# M66_Quectel.net
KiCad netlist of a schematic drawn in Altium Designer
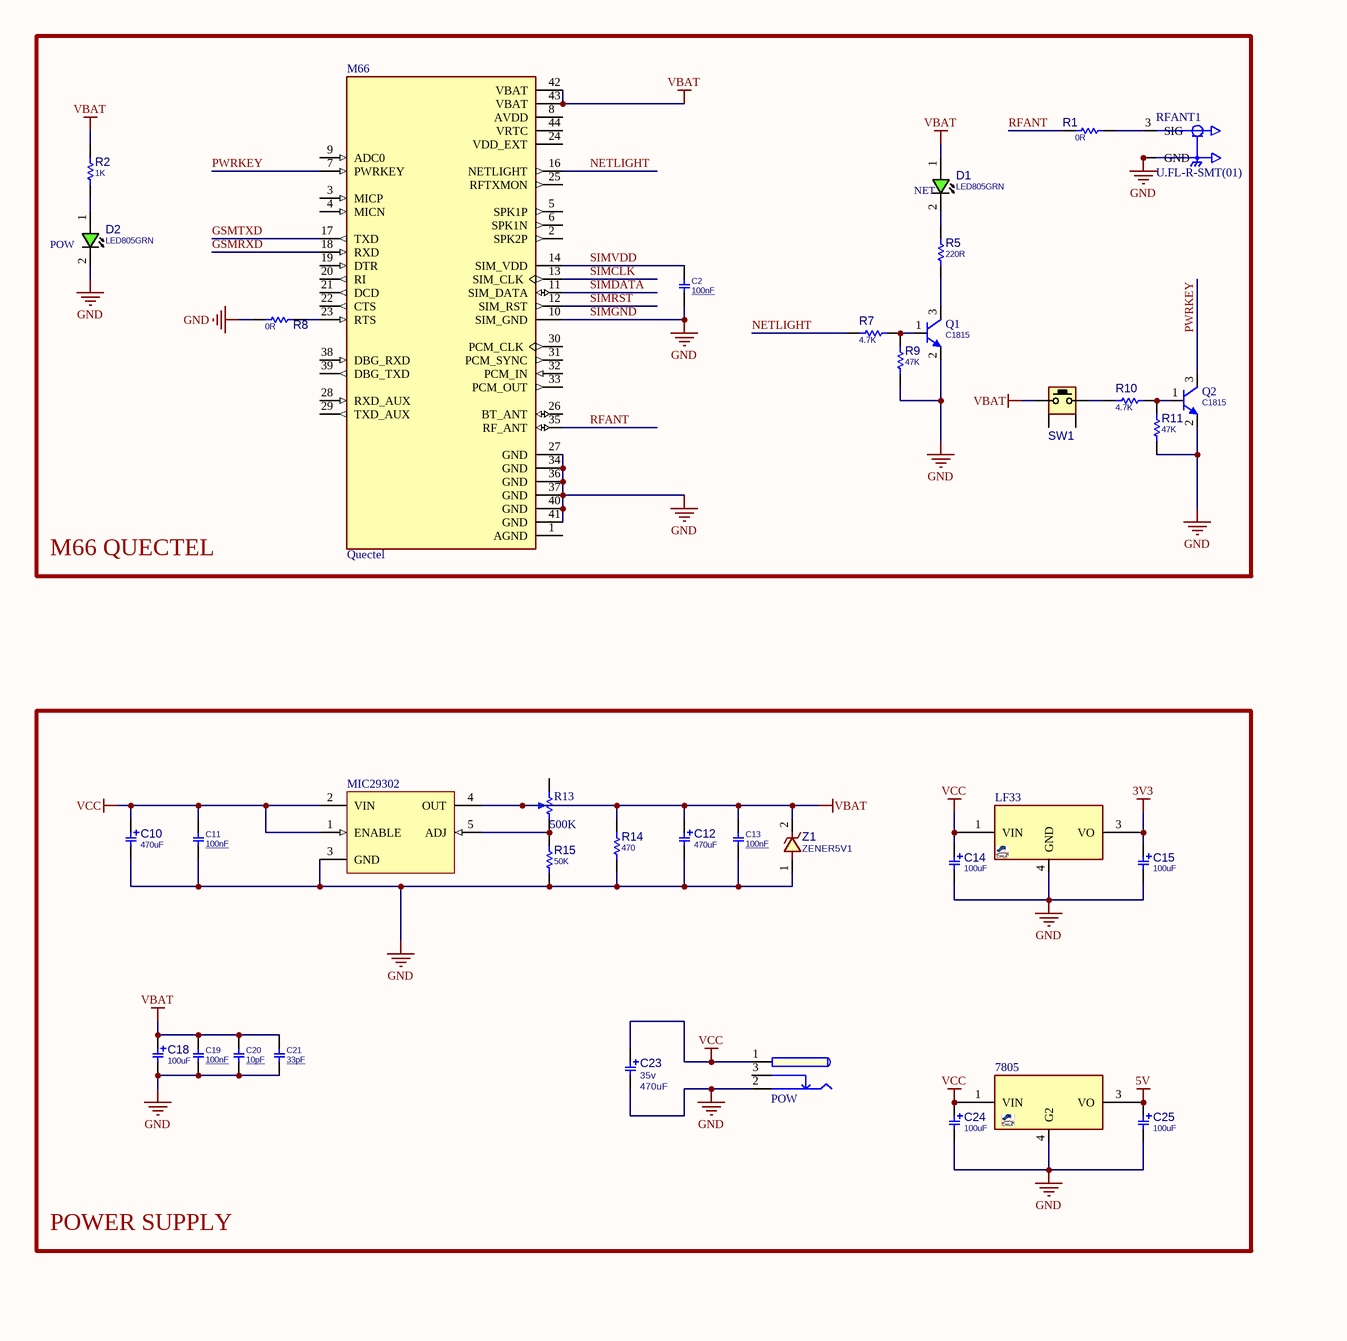
[diagram p0: M66 Quectel.SchDoc, left]
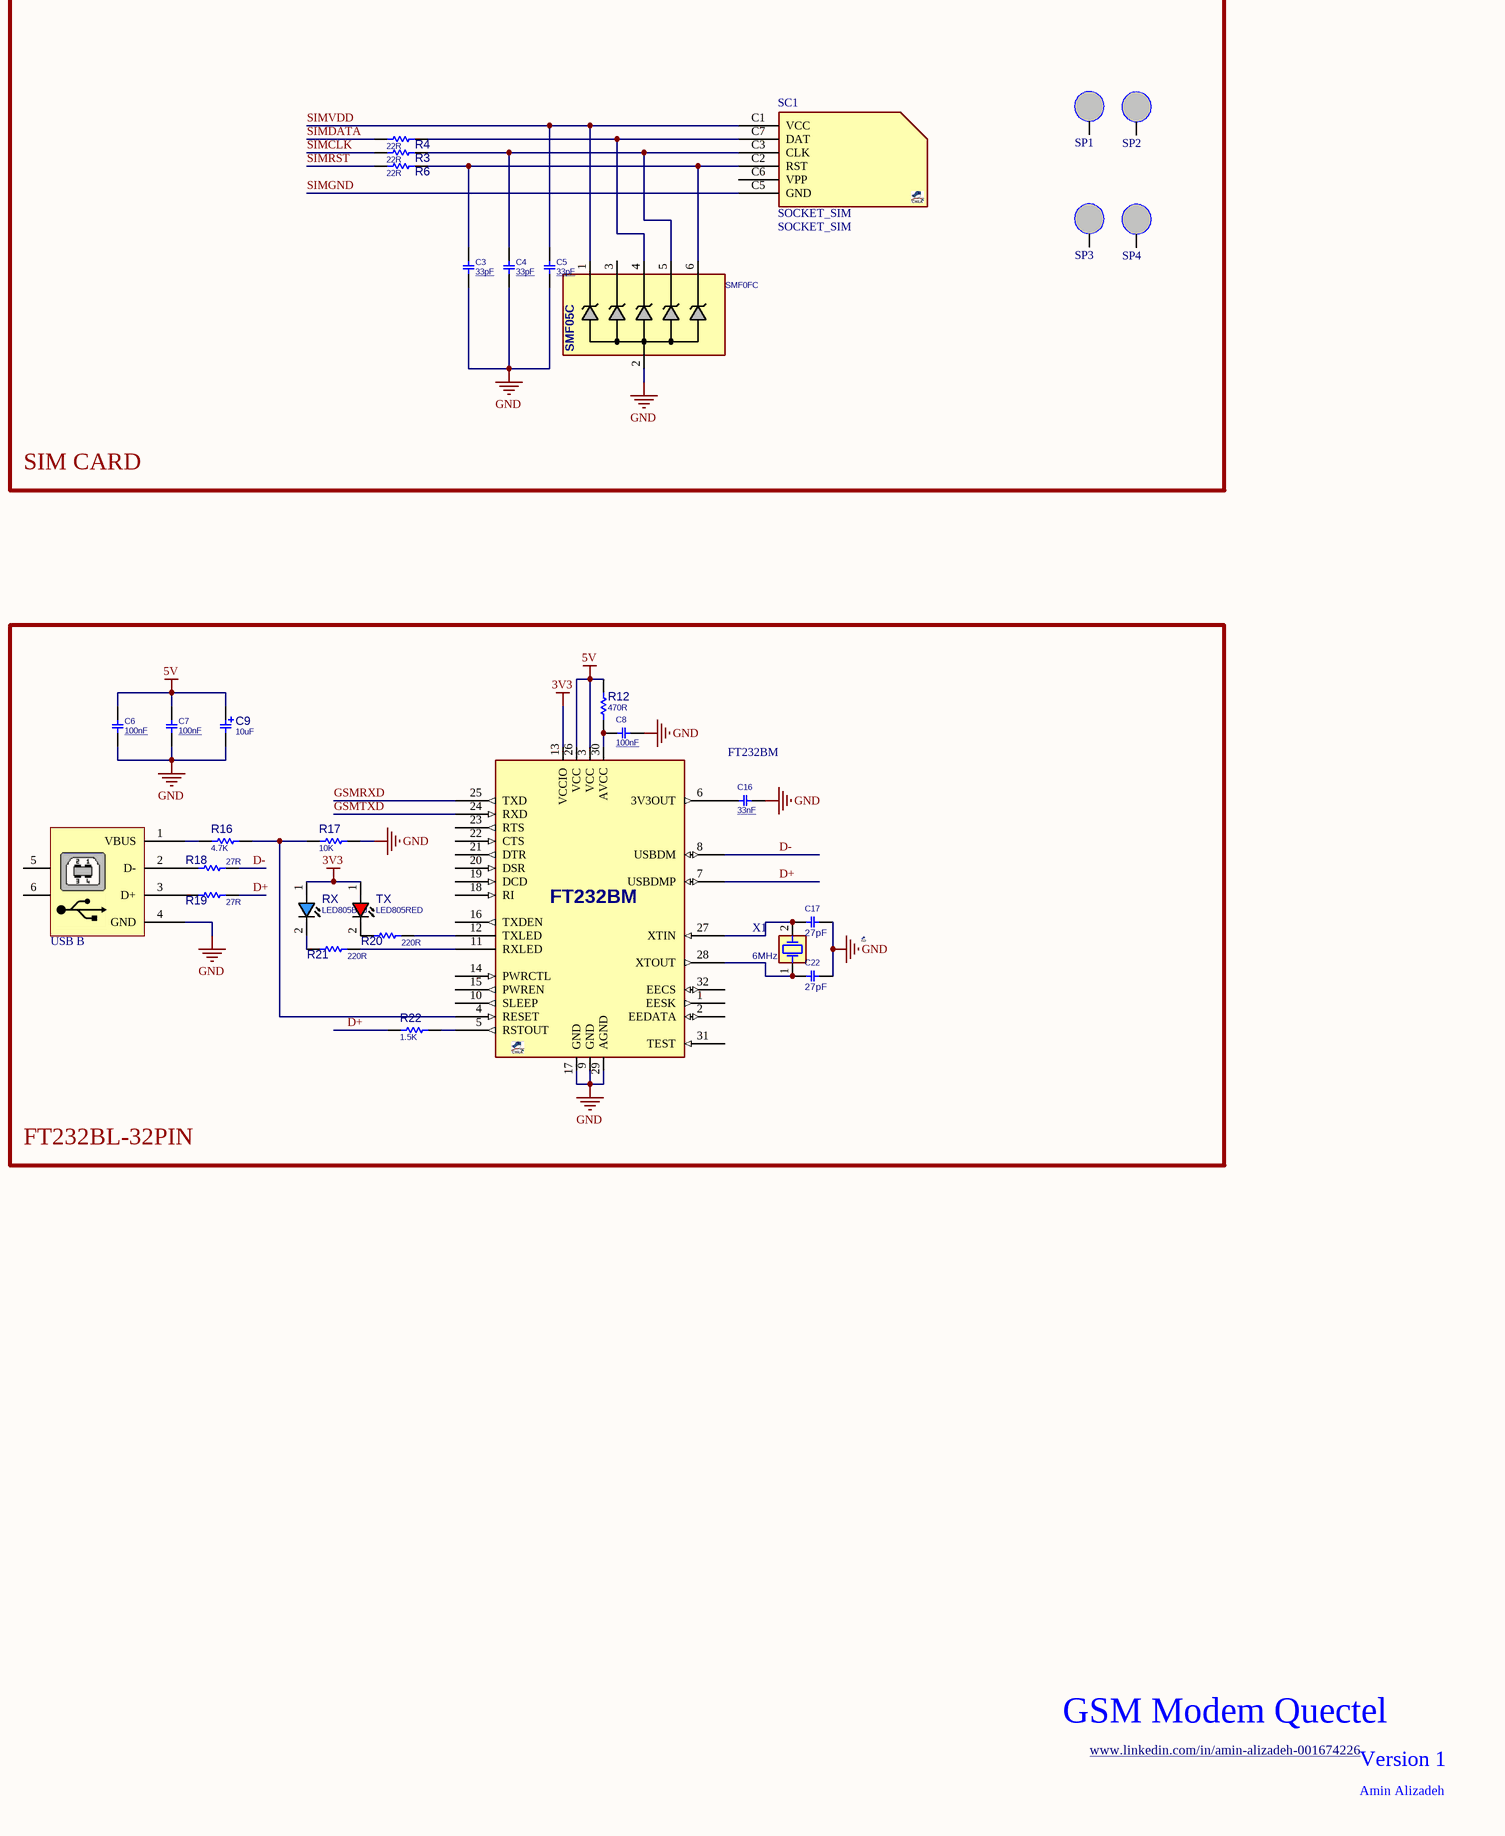
[diagram p1: M66 Quectel.SchDoc, right]

(export (version "E")
  (design (tool "Eeschema 10.0.6"))
  (components
    (comp (ref "7805")
      (value "7805")
      (footprint "D2PAK_2")
      (description "REG, Linear, Fixed, 5v, 1A, TO-263")
      (fields (field (name "MANF_P#") "L7805ABD2T") (field (name "MANF") "TI"))
      (libsource (lib "pwr_reg_linear_78xx79xx") (part "VREG_L7805A_TO263"))
    )
    (comp (ref "C2")
      (value "100nF")
      (footprint "C0805")
      (description "CAP, MLCC, -F, -V, MATERIAL, -%, 0201")
      (fields (field (name "MANF_P#") "MANF_PART#"))
      (libsource (lib "passive_smd") (part "CAP_SMD_MLCC_0805"))
    )
    (comp (ref "C3")
      (value "33pF")
      (footprint "C0805")
      (description "CAP, MLCC, -F, -V, MATERIAL, -%, 0201")
      (fields (field (name "MANF_P#") "MANF_PART#"))
      (libsource (lib "passive_smd") (part "CAP_SMD_MLCC_0805"))
    )
    (comp (ref "C4")
      (value "33pF")
      (footprint "C0805")
      (description "CAP, MLCC, -F, -V, MATERIAL, -%, 0201")
      (fields (field (name "MANF_P#") "MANF_PART#"))
      (libsource (lib "passive_smd") (part "CAP_SMD_MLCC_0805"))
    )
    (comp (ref "C5")
      (value "33pF")
      (footprint "C0805")
      (description "CAP, MLCC, -F, -V, MATERIAL, -%, 0201")
      (fields (field (name "MANF_P#") "MANF_PART#"))
      (libsource (lib "passive_smd") (part "CAP_SMD_MLCC_0805"))
    )
    (comp (ref "C6")
      (value "100nF")
      (footprint "C0805")
      (description "CAP, MLCC, -F, -V, MATERIAL, -%, 0201")
      (fields (field (name "MANF_P#") "MANF_PART#"))
      (libsource (lib "passive_smd") (part "CAP_SMD_MLCC_0805"))
    )
    (comp (ref "C7")
      (value "100nF")
      (footprint "C0805")
      (description "CAP, MLCC, -F, -V, MATERIAL, -%, 0201")
      (fields (field (name "MANF_P#") "MANF_PART#"))
      (libsource (lib "passive_smd") (part "CAP_SMD_MLCC_0805"))
    )
    (comp (ref "C8")
      (value "100nF")
      (footprint "C0805")
      (description "CAP, MLCC, -F, -V, MATERIAL, -%, 0201")
      (fields (field (name "MANF_P#") "MANF_PART#"))
      (libsource (lib "passive_smd") (part "CAP_SMD_MLCC_0805"))
    )
    (comp (ref "C9")
      (value "10uF")
      (footprint "SMD_Cap_10x10")
      (description "CAP, THD, ELEC,")
      (fields (field (name "MANF_P#") "MANF_PART#") (field (name "MANF") "MANF"))
      (libsource (lib "passive_smd") (part "CAP_SMD_EL_8"))
    )
    (comp (ref "C10")
      (value "470uF")
      (footprint "SMD_Cap_10x10")
      (description "CAP, THD, ELEC,")
      (fields (field (name "MANF_P#") "MANF_PART#") (field (name "MANF") "MANF"))
      (libsource (lib "passive_smd") (part "CAP_SMD_EL_8"))
    )
    (comp (ref "C11")
      (value "100nF")
      (footprint "C0805")
      (description "CAP, MLCC, -F, -V, MATERIAL, -%, 0201")
      (fields (field (name "MANF_P#") "MANF_PART#"))
      (libsource (lib "passive_smd") (part "CAP_SMD_MLCC_0805"))
    )
    (comp (ref "C12")
      (value "470uF")
      (footprint "SMD_Cap_10x10")
      (description "CAP, THD, ELEC,")
      (fields (field (name "MANF_P#") "MANF_PART#") (field (name "MANF") "MANF"))
      (libsource (lib "passive_smd") (part "CAP_SMD_EL_8"))
    )
    (comp (ref "C13")
      (value "100nF")
      (footprint "C0805")
      (description "CAP, MLCC, -F, -V, MATERIAL, -%, 0201")
      (fields (field (name "MANF_P#") "MANF_PART#"))
      (libsource (lib "passive_smd") (part "CAP_SMD_MLCC_0805"))
    )
    (comp (ref "C14")
      (value "100uF")
      (footprint "Cap 5.3 x 6.3")
      (description "CAP, THD, ELEC,")
      (fields (field (name "MANF_P#") "MANF_PART#") (field (name "MANF") "MANF"))
      (libsource (lib "passive_smd") (part "CAP_SMD_EL_5"))
    )
    (comp (ref "C15")
      (value "100uF")
      (footprint "Cap 5.3 x 6.3")
      (description "CAP, THD, ELEC,")
      (fields (field (name "MANF_P#") "MANF_PART#") (field (name "MANF") "MANF"))
      (libsource (lib "passive_smd") (part "CAP_SMD_EL_5"))
    )
    (comp (ref "C16")
      (value "33nF")
      (footprint "C0805")
      (description "CAP, MLCC, -F, -V, MATERIAL, -%, 0201")
      (fields (field (name "MANF_P#") "MANF_PART#"))
      (libsource (lib "passive_smd") (part "CAP_SMD_MLCC_0805"))
    )
    (comp (ref "C17")
      (value "27pF")
      (footprint "C0805")
      (description "CAP, MLCC")
      (fields (field (name "MANF_P#") "MANF_PART#"))
      (libsource (lib "passive_smd") (part "CAP_SMD_MLCC_0805"))
    )
    (comp (ref "C18")
      (value "100uF")
      (footprint "SMD_Cap_10x10")
      (description "CAP, THD, ELEC,")
      (fields (field (name "MANF_P#") "MANF_PART#") (field (name "MANF") "MANF"))
      (libsource (lib "passive_smd") (part "CAP_SMD_EL_8"))
    )
    (comp (ref "C19")
      (value "100nF")
      (footprint "C0805")
      (description "CAP, MLCC, -F, -V, MATERIAL, -%, 0201")
      (fields (field (name "MANF_P#") "MANF_PART#"))
      (libsource (lib "passive_smd") (part "CAP_SMD_MLCC_0805"))
    )
    (comp (ref "C20")
      (value "10pF")
      (footprint "C0805")
      (description "CAP, MLCC, -F, -V, MATERIAL, -%, 0201")
      (fields (field (name "MANF_P#") "MANF_PART#"))
      (libsource (lib "passive_smd") (part "CAP_SMD_MLCC_0805"))
    )
    (comp (ref "C21")
      (value "33pF")
      (footprint "C0805")
      (description "CAP, MLCC, -F, -V, MATERIAL, -%, 0201")
      (fields (field (name "MANF_P#") "MANF_PART#"))
      (libsource (lib "passive_smd") (part "CAP_SMD_MLCC_0805"))
    )
    (comp (ref "C22")
      (value "27pF")
      (footprint "C0805")
      (description "CAP, MLCC")
      (fields (field (name "MANF_P#") "MANF_PART#"))
      (libsource (lib "passive_smd") (part "CAP_SMD_MLCC_0805"))
    )
    (comp (ref "C23")
      (value "470uF")
      (footprint "SMD_Cap_10x10")
      (description "CAP, SMD, ELEC,")
      (fields
        (field (name "MANF_P#") "MANF_PART#")
        (field (name "MANF") "MANF")
        (field (name "PARAM2") "35v")
      )
      (libsource (lib "passive_smd") (part "CAP_SMD_EL_470uF_35v"))
    )
    (comp (ref "C24")
      (value "100uF")
      (footprint "Cap 5.3 x 6.3")
      (description "CAP, THD, ELEC,")
      (fields (field (name "MANF_P#") "MANF_PART#") (field (name "MANF") "MANF"))
      (libsource (lib "passive_smd") (part "CAP_SMD_EL_5"))
    )
    (comp (ref "C25")
      (value "100uF")
      (footprint "Cap 5.3 x 6.3")
      (description "CAP, THD, ELEC,")
      (fields (field (name "MANF_P#") "MANF_PART#") (field (name "MANF") "MANF"))
      (libsource (lib "passive_smd") (part "CAP_SMD_EL_5"))
    )
    (comp (ref "D1")
      (value "NET")
      (footprint "LED0805GRN")
      (description "LED, SMD, 0805, GREEN")
      (fields (field (name "ALTIUM_VALUE") "LED805GRN"))
      (libsource (lib "led(diode)") (part "LED_SMD_0805_GRN"))
    )
    (comp (ref "D2")
      (value "POW")
      (footprint "LED0805GRN")
      (description "LED, SMD, 0805, GREEN")
      (fields (field (name "ALTIUM_VALUE") "LED805GRN"))
      (libsource (lib "led(diode)") (part "LED_SMD_0805_GRN"))
    )
    (comp (ref "FT232BM")
      (value "FT232BM")
      (footprint "QFG80_32")
      (description "USB-UART")
      (fields (field (name "MANF") "FTDI"))
      (libsource (lib "usbic") (part "FT232BM_QFP32"))
    )
    (comp (ref "LF33")
      (value "LF33")
      (footprint "DPAK_3")
      (description "REG, Linear, LDO0.45V, 0.5A, TO-252")
      (fields (field (name "MANF") "ST"))
      (libsource (lib "pwr_reg_linear") (part "VREG_LFXX_TO252"))
    )
    (comp (ref "M66")
      (value "Quectel")
      (footprint "XCVR_M66")
      (fields (field (name "MP") "M66"))
      (libsource (lib "M66") (part "M66"))
    )
    (comp (ref "MIC29302")
      (value "MIC29XX")
      (footprint "D2PAK_5")
      (description "High-Current Low-Dropout Regulators")
      (libsource (lib "OMID_DXP_LIB93") (part "MIC29302"))
    )
    (comp (ref "POW")
      (value "DC Power Jack")
      (footprint "DC_Power_Jack")
      (libsource (lib "Sajad_Altium_Library") (part "DC_Power_Jack"))
    )
    (comp (ref "Q1")
      (value "C1815")
      (footprint "SOT23_3")
      (description "BJT, NPN, 50v, 0.15A, SMD, SOT23")
      (libsource (lib "transistor_bjt") (part "NPN_C1815_SOT23"))
    )
    (comp (ref "Q2")
      (value "C1815")
      (footprint "SOT23_3")
      (description "BJT, NPN, 50v, 0.15A, SMD, SOT23")
      (libsource (lib "transistor_bjt") (part "NPN_C1815_SOT23"))
    )
    (comp (ref "R1")
      (value "0R")
      (footprint "R0805")
      (description "RESISTOR, SMD")
      (libsource (lib "passive_smd") (part "RES_SMD_0805"))
    )
    (comp (ref "R2")
      (value "1K")
      (footprint "R0805")
      (description "RESISTOR, SMD")
      (libsource (lib "passive_smd") (part "RES_SMD_0805"))
    )
    (comp (ref "R3")
      (value "22R")
      (footprint "R0805")
      (description "RESISTOR, SMD")
      (libsource (lib "passive_smd") (part "RES_SMD_0805"))
    )
    (comp (ref "R4")
      (value "22R")
      (footprint "R0805")
      (description "RESISTOR, SMD")
      (libsource (lib "passive_smd") (part "RES_SMD_0805"))
    )
    (comp (ref "R5")
      (value "220R")
      (footprint "R0805")
      (description "RESISTOR, SMD")
      (libsource (lib "passive_smd") (part "RES_SMD_0805"))
    )
    (comp (ref "R6")
      (value "22R")
      (footprint "R0805")
      (description "RESISTOR, SMD")
      (libsource (lib "passive_smd") (part "RES_SMD_0805"))
    )
    (comp (ref "R7")
      (value "4.7K")
      (footprint "R0805")
      (description "RESISTOR, SMD")
      (libsource (lib "passive_smd") (part "RES_SMD_0805"))
    )
    (comp (ref "R8")
      (value "0R")
      (footprint "R0805")
      (description "RESISTOR, SMD")
      (libsource (lib "passive_smd") (part "RES_SMD_0805"))
    )
    (comp (ref "R9")
      (value "47K")
      (footprint "R0805")
      (description "RESISTOR, SMD")
      (libsource (lib "passive_smd") (part "RES_SMD_0805"))
    )
    (comp (ref "R10")
      (value "4.7K")
      (footprint "R0805")
      (description "RESISTOR, SMD")
      (libsource (lib "passive_smd") (part "RES_SMD_0805"))
    )
    (comp (ref "R11")
      (value "47K")
      (footprint "R0805")
      (description "RESISTOR, SMD")
      (libsource (lib "passive_smd") (part "RES_SMD_0805"))
    )
    (comp (ref "R12")
      (value "470R")
      (footprint "R0805")
      (description "RESISTOR, SMD")
      (libsource (lib "passive_smd") (part "RES_SMD_0805"))
    )
    (comp (ref "R13")
      (value "500K")
      (footprint "POT_3296W")
      (description "Potentiometer MULTI TURN")
      (fields (field (name "Comment") "Multi_turn") (field (name "PUBLISHER") "Altium Limited"))
      (libsource (lib "OMID_DXP_LIB93") (part "Multi_turn"))
    )
    (comp (ref "R14")
      (value "470")
      (footprint "R0805")
      (description "RESISTOR, SMD")
      (libsource (lib "passive_smd") (part "RES_SMD_0805"))
    )
    (comp (ref "R15")
      (value "50K")
      (footprint "R0805")
      (description "RESISTOR, SMD")
      (libsource (lib "passive_smd") (part "RES_SMD_0805"))
    )
    (comp (ref "R16")
      (value "4.7K")
      (footprint "R0805")
      (description "RESISTOR, SMD")
      (libsource (lib "passive_smd") (part "RES_SMD_0805"))
    )
    (comp (ref "R17")
      (value "10K")
      (footprint "R0805")
      (description "RESISTOR, SMD")
      (libsource (lib "passive_smd") (part "RES_SMD_0805"))
    )
    (comp (ref "R18")
      (value "27R")
      (footprint "R0805")
      (description "RESISTOR, SMD")
      (libsource (lib "passive_smd") (part "RES_SMD_0805"))
    )
    (comp (ref "R19")
      (value "27R")
      (footprint "R0805")
      (description "RESISTOR, SMD")
      (libsource (lib "passive_smd") (part "RES_SMD_0805"))
    )
    (comp (ref "R20")
      (value "220R")
      (footprint "R0805")
      (description "RESISTOR, SMD")
      (libsource (lib "passive_smd") (part "RES_SMD_0805"))
    )
    (comp (ref "R21")
      (value "220R")
      (footprint "R0805")
      (description "RESISTOR, SMD")
      (libsource (lib "passive_smd") (part "RES_SMD_0805"))
    )
    (comp (ref "R22")
      (value "1.5K")
      (footprint "R0805")
      (description "RESISTOR, SMD")
      (libsource (lib "passive_smd") (part "RES_SMD_0805"))
    )
    (comp (ref "RFANT1")
      (value "U.FL-R-SMT(01)")
      (footprint "HRS_U.FL-R-SMT(01)")
      (fields (field (name "MF") "Hirose"))
      (libsource (lib "U.FL-R-SMT_01_") (part "U.FL-R-SMT(01)"))
    )
    (comp (ref "RX")
      (value "LED805BLU")
      (footprint "LED0805BLU")
      (description "LED, SMD, 0805, BLUE")
      (fields (field (name "MANF") "MANF") (field (name "MANF_P#") "MANF_PART#"))
      (libsource (lib "led(diode)") (part "LED_SMD_0805_BLU"))
    )
    (comp (ref "SC1")
      (value "SOCKET_SIM")
      (footprint "SIM_MINI_6JT")
      (description "SOCKET, SIM MINI, PUSH-PULL, exist on Iran")
      (fields (field (name "MANF") "JTCONN") (field (name "ALTIUM_VALUE") "SOCKET_SIM"))
      (libsource (lib "socket_card") (part "SIM_MINI_6_JT"))
    )
    (comp (ref "SMF0FC")
      (value "TVS_SMF05C")
      (footprint "SOT363_6")
      (description "TVS, ESD PROTECT, 5CH, 5VRWM, 15KV")
      (fields (field (name "MANF_P#") "SMF05C, SMF05CT1G") (field (name "MANF") "Semtech, ON"))
      (libsource (lib "protect_tvs_esd_fuse") (part "TVS_X5_SMF05C"))
    )
    (comp (ref "SP1")
      (value "Spacer")
      (footprint "my_space")
      (description "10MM SPACER")
      (libsource (lib "OMID_DXP_LIB93") (part "Spacer"))
    )
    (comp (ref "SP2")
      (value "Spacer")
      (footprint "my_space")
      (description "10MM SPACER")
      (libsource (lib "OMID_DXP_LIB93") (part "Spacer"))
    )
    (comp (ref "SP3")
      (value "Spacer")
      (footprint "my_space")
      (description "10MM SPACER")
      (libsource (lib "OMID_DXP_LIB93") (part "Spacer"))
    )
    (comp (ref "SP4")
      (value "Spacer")
      (footprint "my_space")
      (description "10MM SPACER")
      (libsource (lib "OMID_DXP_LIB93") (part "Spacer"))
    )
    (comp (ref "SW1")
      (value "POW ON")
      (footprint "SWPBT_SPST_R_6X6X10")
      (description "SWITCH, PUSH BUTTON, TACTILE, THD, SPST, RIGHT")
      (libsource (lib "switch_tact_PUSHB") (part "SWPBT_SPST_R_6X6X10"))
    )
    (comp (ref "TX")
      (value "LED805RED")
      (footprint "LED0805RED")
      (description "LED, SMD, 0805, RED")
      (fields (field (name "MANF") "MANF") (field (name "MANF_P#") "MANF_PART#"))
      (libsource (lib "led(diode)") (part "LED_SMD_0805_RED"))
    )
    (comp (ref "USB B")
      (value "USB_B")
      (footprint "USB_B.1")
      (description "USB B")
      (fields (field (name "PUBLISHER") "Altium Limited"))
      (libsource (lib "A.Mohebbi") (part "USB_B"))
    )
    (comp (ref "X1")
      (value "6MHz")
      (footprint "XTL_2_11X5")
      (description "Crystal MOST POPULAR ABL HC49 PACKAGE")
      (fields (field (name "MANF") "ABRACON") (field (name "MANF_P#") "ABLS-8.000MHZ-B4-T"))
      (libsource (lib "crystal") (part "XTL_2_HC49_8MHz_SMD"))
    )
    (comp (ref "Z1")
      (value "ZENER5V1")
      (footprint "D_SOD123W")
      (description "DIODE, ZENER, 1W, 5.1V")
      (fields (field (name "MANF") "Diodes") (field (name "MANF_P#") "BZT52HC5V1WF-7"))
      (libsource (lib "diode") (part "DIODE_SMD_ZENER_BZT52HC5V1"))
    )
  )
  (nets
    (net (code "1") (name "/D+") (class "Default")
      (node (ref "FT232BM") (pin "7") (pinfunction "USBDMP_7") (pintype "bidirectional"))
      (node (ref "R19") (pin "1") (pinfunction "1_1") (pintype "passive"))
      (node (ref "R22") (pin "2") (pinfunction "2_2") (pintype "passive"))
    )
    (net (code "2") (name "/D-") (class "Default")
      (node (ref "FT232BM") (pin "8") (pinfunction "USBDM_8") (pintype "bidirectional"))
      (node (ref "R18") (pin "1") (pinfunction "1_1") (pintype "passive"))
    )
    (net (code "3") (name "/GSMRXD") (class "Default")
      (node (ref "FT232BM") (pin "25") (pinfunction "TXD_25") (pintype "output"))
      (node (ref "M66") (pin "18") (pinfunction "RXD_18") (pintype "input"))
    )
    (net (code "4") (name "/GSMTXD") (class "Default")
      (node (ref "FT232BM") (pin "24") (pinfunction "RXD_24") (pintype "input"))
      (node (ref "M66") (pin "17") (pinfunction "TXD_17") (pintype "output"))
    )
    (net (code "5") (name "/NETLIGHT") (class "Default")
      (node (ref "M66") (pin "16") (pinfunction "NETLIGHT_16") (pintype "output"))
      (node (ref "R7") (pin "2") (pinfunction "2_2") (pintype "passive"))
    )
    (net (code "6") (name "/PWRKEY") (class "Default")
      (node (ref "M66") (pin "7") (pinfunction "PWRKEY_7") (pintype "input"))
      (node (ref "Q2") (pin "3") (pinfunction "C_3") (pintype "passive"))
    )
    (net (code "7") (name "/RFANT") (class "Default")
      (node (ref "M66") (pin "35") (pinfunction "RF_ANT_35") (pintype "bidirectional"))
      (node (ref "R1") (pin "2") (pinfunction "2_2") (pintype "passive"))
    )
    (net (code "8") (name "/SIMCLK") (class "Default")
      (node (ref "M66") (pin "13") (pinfunction "SIM_CLK_13") (pintype "output"))
      (node (ref "R3") (pin "2") (pinfunction "2_2") (pintype "passive"))
    )
    (net (code "9") (name "/SIMDATA") (class "Default")
      (node (ref "M66") (pin "11") (pinfunction "SIM_DATA_11") (pintype "bidirectional"))
      (node (ref "R4") (pin "2") (pinfunction "2_2") (pintype "passive"))
    )
    (net (code "10") (name "/SIMRST") (class "Default")
      (node (ref "M66") (pin "12") (pinfunction "SIM_RST_12") (pintype "output"))
      (node (ref "R6") (pin "2") (pinfunction "2_2") (pintype "passive"))
    )
    (net (code "11") (name "/SIMVDD") (class "Default")
      (node (ref "C2") (pin "2") (pinfunction "2_2") (pintype "passive"))
      (node (ref "C5") (pin "2") (pinfunction "2_2") (pintype "passive"))
      (node (ref "M66") (pin "14") (pinfunction "SIM_VDD_14") (pintype "power_in"))
      (node (ref "SC1") (pin "C1") (pinfunction "VCC_C1") (pintype "passive"))
      (node (ref "SMF0FC") (pin "1") (pinfunction "1_1") (pintype "passive"))
    )
    (net (code "12") (name "3V3") (class "Default")
      (node (ref "C15") (pin "1") (pinfunction "1_1") (pintype "passive"))
      (node (ref "FT232BM") (pin "13") (pinfunction "VCCIO_13") (pintype "power_in"))
      (node (ref "LF33") (pin "3") (pinfunction "VO_3") (pintype "passive"))
      (node (ref "RX") (pin "1") (pinfunction "ANODE_1") (pintype "passive"))
      (node (ref "TX") (pin "1") (pinfunction "ANODE_1") (pintype "passive"))
    )
    (net (code "13") (name "5V") (class "Default")
      (node (ref "7805") (pin "3") (pinfunction "VO_3") (pintype "passive"))
      (node (ref "C25") (pin "1") (pinfunction "1_1") (pintype "passive"))
      (node (ref "C6") (pin "1") (pinfunction "1_1") (pintype "passive"))
      (node (ref "C7") (pin "1") (pinfunction "1_1") (pintype "passive"))
      (node (ref "C9") (pin "1") (pinfunction "1_1") (pintype "passive"))
      (node (ref "FT232BM") (pin "26") (pinfunction "VCC_26") (pintype "power_in"))
      (node (ref "FT232BM") (pin "3") (pinfunction "VCC_3") (pintype "power_in"))
      (node (ref "R12") (pin "2") (pinfunction "2_2") (pintype "passive"))
    )
    (net (code "14") (name "GND") (class "Default")
      (node (ref "7805") (pin "4") (pinfunction "G2_4") (pintype "passive"))
      (node (ref "C10") (pin "2") (pinfunction "2_2") (pintype "passive"))
      (node (ref "C11") (pin "1") (pinfunction "1_1") (pintype "passive"))
      (node (ref "C12") (pin "2") (pinfunction "2_2") (pintype "passive"))
      (node (ref "C13") (pin "1") (pinfunction "1_1") (pintype "passive"))
      (node (ref "C14") (pin "2") (pinfunction "2_2") (pintype "passive"))
      (node (ref "C15") (pin "2") (pinfunction "2_2") (pintype "passive"))
      (node (ref "C16") (pin "2") (pinfunction "2_2") (pintype "passive"))
      (node (ref "C17") (pin "1") (pinfunction "1_1") (pintype "passive"))
      (node (ref "C18") (pin "2") (pinfunction "2_2") (pintype "passive"))
      (node (ref "C19") (pin "1") (pinfunction "1_1") (pintype "passive"))
      (node (ref "C2") (pin "1") (pinfunction "1_1") (pintype "passive"))
      (node (ref "C20") (pin "1") (pinfunction "1_1") (pintype "passive"))
      (node (ref "C21") (pin "1") (pinfunction "1_1") (pintype "passive"))
      (node (ref "C22") (pin "1") (pinfunction "1_1") (pintype "passive"))
      (node (ref "C23") (pin "2") (pinfunction "2_2") (pintype "passive"))
      (node (ref "C24") (pin "2") (pinfunction "2_2") (pintype "passive"))
      (node (ref "C25") (pin "2") (pinfunction "2_2") (pintype "passive"))
      (node (ref "C3") (pin "1") (pinfunction "1_1") (pintype "passive"))
      (node (ref "C4") (pin "1") (pinfunction "1_1") (pintype "passive"))
      (node (ref "C5") (pin "1") (pinfunction "1_1") (pintype "passive"))
      (node (ref "C6") (pin "2") (pinfunction "2_2") (pintype "passive"))
      (node (ref "C7") (pin "2") (pinfunction "2_2") (pintype "passive"))
      (node (ref "C8") (pin "1") (pinfunction "1_1") (pintype "passive"))
      (node (ref "C9") (pin "2") (pinfunction "2_2") (pintype "passive"))
      (node (ref "D2") (pin "2") (pinfunction "CATHODE_2") (pintype "passive"))
      (node (ref "FT232BM") (pin "17") (pinfunction "GND_17") (pintype "power_in"))
      (node (ref "FT232BM") (pin "29") (pinfunction "AGND_29") (pintype "power_in"))
      (node (ref "FT232BM") (pin "9") (pinfunction "GND_9") (pintype "power_in"))
      (node (ref "LF33") (pin "4") (pinfunction "GND_4") (pintype "passive"))
      (node (ref "M66") (pin "10") (pinfunction "SIM_GND_10") (pintype "power_in"))
      (node (ref "M66") (pin "27") (pinfunction "GND_27") (pintype "power_in"))
      (node (ref "M66") (pin "34") (pinfunction "GND_34") (pintype "power_in"))
      (node (ref "M66") (pin "36") (pinfunction "GND_36") (pintype "power_in"))
      (node (ref "M66") (pin "37") (pinfunction "GND_37") (pintype "power_in"))
      (node (ref "M66") (pin "40") (pinfunction "GND_40") (pintype "power_in"))
      (node (ref "M66") (pin "41") (pinfunction "GND_41") (pintype "power_in"))
      (node (ref "MIC29302") (pin "3") (pinfunction "GND_3") (pintype "power_in"))
      (node (ref "POW") (pin "2") (pinfunction "GND_2") (pintype "power_in"))
      (node (ref "Q1") (pin "2") (pinfunction "E_2") (pintype "passive"))
      (node (ref "Q2") (pin "2") (pinfunction "E_2") (pintype "passive"))
      (node (ref "R11") (pin "1") (pinfunction "1_1") (pintype "passive"))
      (node (ref "R14") (pin "1") (pinfunction "1_1") (pintype "passive"))
      (node (ref "R15") (pin "1") (pinfunction "1_1") (pintype "passive"))
      (node (ref "R17") (pin "2") (pinfunction "2_2") (pintype "passive"))
      (node (ref "R8") (pin "2") (pinfunction "2_2") (pintype "passive"))
      (node (ref "R9") (pin "1") (pinfunction "1_1") (pintype "passive"))
      (node (ref "RFANT1") (pin "1") (pinfunction "GND_1") (pintype "passive"))
      (node (ref "RFANT1") (pin "2") (pinfunction "GND_2") (pintype "passive"))
      (node (ref "SC1") (pin "C5") (pinfunction "GND_C5") (pintype "passive"))
      (node (ref "SMF0FC") (pin "2") (pinfunction "2_2") (pintype "passive"))
      (node (ref "USB B") (pin "4") (pinfunction "GND_4") (pintype "power_in"))
      (node (ref "Z1") (pin "1") (pinfunction "1_1") (pintype "passive"))
    )
    (net (code "15") (name "Net-(D1-CATHODE)") (class "Default")
      (node (ref "D1") (pin "2") (pinfunction "CATHODE_2") (pintype "passive"))
      (node (ref "R5") (pin "2") (pinfunction "2_2") (pintype "passive"))
    )
    (net (code "16") (name "Net-(D2-ANODE)") (class "Default")
      (node (ref "D2") (pin "1") (pinfunction "ANODE_1") (pintype "passive"))
      (node (ref "R2") (pin "1") (pinfunction "1_1") (pintype "passive"))
    )
    (net (code "17") (name "Net-(FT232BM-3V3OUT)") (class "Default")
      (node (ref "C16") (pin "1") (pinfunction "1_1") (pintype "passive"))
      (node (ref "FT232BM") (pin "6") (pinfunction "3V3OUT_6") (pintype "output"))
    )
    (net (code "18") (name "Net-(FT232BM-AVCC)") (class "Default")
      (node (ref "C8") (pin "2") (pinfunction "2_2") (pintype "passive"))
      (node (ref "FT232BM") (pin "30") (pinfunction "AVCC_30") (pintype "power_in"))
      (node (ref "R12") (pin "1") (pinfunction "1_1") (pintype "passive"))
    )
    (net (code "19") (name "Net-(FT232BM-RESET)") (class "Default")
      (node (ref "FT232BM") (pin "4") (pinfunction "RESET_4") (pintype "input"))
      (node (ref "R16") (pin "2") (pinfunction "2_2") (pintype "passive"))
      (node (ref "R17") (pin "1") (pinfunction "1_1") (pintype "passive"))
    )
    (net (code "20") (name "Net-(FT232BM-RSTOUT)") (class "Default")
      (node (ref "FT232BM") (pin "5") (pinfunction "RSTOUT_5") (pintype "output"))
      (node (ref "R22") (pin "1") (pinfunction "1_1") (pintype "passive"))
    )
    (net (code "21") (name "Net-(FT232BM-RXLED)") (class "Default")
      (node (ref "FT232BM") (pin "11") (pinfunction "RXLED_11") (pintype "open_collector"))
      (node (ref "R21") (pin "1") (pinfunction "1_1") (pintype "passive"))
    )
    (net (code "22") (name "Net-(FT232BM-TXLED)") (class "Default")
      (node (ref "FT232BM") (pin "12") (pinfunction "TXLED_12") (pintype "open_collector"))
      (node (ref "R20") (pin "1") (pinfunction "1_1") (pintype "passive"))
    )
    (net (code "23") (name "Net-(FT232BM-XTIN)") (class "Default")
      (node (ref "C17") (pin "2") (pinfunction "2_2") (pintype "passive"))
      (node (ref "FT232BM") (pin "27") (pinfunction "XTIN_27") (pintype "input"))
      (node (ref "X1") (pin "2") (pinfunction "OSC2_2") (pintype "passive"))
    )
    (net (code "24") (name "Net-(FT232BM-XTOUT)") (class "Default")
      (node (ref "C22") (pin "2") (pinfunction "2_2") (pintype "passive"))
      (node (ref "FT232BM") (pin "28") (pinfunction "XTOUT_28") (pintype "output"))
      (node (ref "X1") (pin "1") (pinfunction "OSC1_1") (pintype "passive"))
    )
    (net (code "25") (name "Net-(M66-RTS)") (class "Default")
      (node (ref "M66") (pin "23") (pinfunction "RTS_23") (pintype "input"))
      (node (ref "R8") (pin "1") (pinfunction "1_1") (pintype "passive"))
    )
    (net (code "26") (name "Net-(MIC29302-ADJ)") (class "Default")
      (node (ref "MIC29302") (pin "5") (pinfunction "ADJ_5") (pintype "input"))
      (node (ref "R13") (pin "2") (pinfunction "BOT_2") (pintype "passive"))
      (node (ref "R15") (pin "2") (pinfunction "2_2") (pintype "passive"))
    )
    (net (code "27") (name "Net-(Q1-B)") (class "Default")
      (node (ref "Q1") (pin "1") (pinfunction "B_1") (pintype "passive"))
      (node (ref "R7") (pin "1") (pinfunction "1_1") (pintype "passive"))
      (node (ref "R9") (pin "2") (pinfunction "2_2") (pintype "passive"))
    )
    (net (code "28") (name "Net-(Q1-C)") (class "Default")
      (node (ref "Q1") (pin "3") (pinfunction "C_3") (pintype "passive"))
      (node (ref "R5") (pin "1") (pinfunction "1_1") (pintype "passive"))
    )
    (net (code "29") (name "Net-(Q2-B)") (class "Default")
      (node (ref "Q2") (pin "1") (pinfunction "B_1") (pintype "passive"))
      (node (ref "R10") (pin "1") (pinfunction "1_1") (pintype "passive"))
      (node (ref "R11") (pin "2") (pinfunction "2_2") (pintype "passive"))
    )
    (net (code "30") (name "Net-(R10-Pad2)") (class "Default")
      (node (ref "R10") (pin "2") (pinfunction "2_2") (pintype "passive"))
      (node (ref "SW1") (pin "2") (pinfunction "2_2") (pintype "passive"))
    )
    (net (code "31") (name "Net-(RFANT1-SIG)") (class "Default")
      (node (ref "R1") (pin "1") (pinfunction "1_1") (pintype "passive"))
      (node (ref "RFANT1") (pin "3") (pinfunction "SIG_3") (pintype "passive"))
    )
    (net (code "32") (name "Net-(RX-CATHODE)") (class "Default")
      (node (ref "R21") (pin "2") (pinfunction "2_2") (pintype "passive"))
      (node (ref "RX") (pin "2") (pinfunction "CATHODE_2") (pintype "passive"))
    )
    (net (code "33") (name "Net-(SC1-CLK)") (class "Default")
      (node (ref "C4") (pin "2") (pinfunction "2_2") (pintype "passive"))
      (node (ref "R3") (pin "1") (pinfunction "1_1") (pintype "passive"))
      (node (ref "SC1") (pin "C3") (pinfunction "CLK_C3") (pintype "passive"))
      (node (ref "SMF0FC") (pin "5") (pinfunction "5_5") (pintype "passive"))
    )
    (net (code "34") (name "Net-(SC1-DAT)") (class "Default")
      (node (ref "R4") (pin "1") (pinfunction "1_1") (pintype "passive"))
      (node (ref "SC1") (pin "C7") (pinfunction "DAT_C7") (pintype "passive"))
      (node (ref "SMF0FC") (pin "4") (pinfunction "4_4") (pintype "passive"))
    )
    (net (code "35") (name "Net-(SC1-RST)") (class "Default")
      (node (ref "C3") (pin "2") (pinfunction "2_2") (pintype "passive"))
      (node (ref "R6") (pin "1") (pinfunction "1_1") (pintype "passive"))
      (node (ref "SC1") (pin "C2") (pinfunction "RST_C2") (pintype "passive"))
      (node (ref "SMF0FC") (pin "6") (pinfunction "6_6") (pintype "passive"))
    )
    (net (code "36") (name "Net-(TX-CATHODE)") (class "Default")
      (node (ref "R20") (pin "2") (pinfunction "2_2") (pintype "passive"))
      (node (ref "TX") (pin "2") (pinfunction "CATHODE_2") (pintype "passive"))
    )
    (net (code "37") (name "Net-(USB B-D+)") (class "Default")
      (node (ref "R19") (pin "2") (pinfunction "2_2") (pintype "passive"))
      (node (ref "USB B") (pin "3") (pinfunction "D+_3") (pintype "passive"))
    )
    (net (code "38") (name "Net-(USB B-D-)") (class "Default")
      (node (ref "R18") (pin "2") (pinfunction "2_2") (pintype "passive"))
      (node (ref "USB B") (pin "2") (pinfunction "D-_2") (pintype "passive"))
    )
    (net (code "39") (name "Net-(USB B-VBUS)") (class "Default")
      (node (ref "R16") (pin "1") (pinfunction "1_1") (pintype "passive"))
      (node (ref "USB B") (pin "1") (pinfunction "VBUS_1") (pintype "power_in"))
    )
    (net (code "40") (name "VBAT") (class "Default")
      (node (ref "C12") (pin "1") (pinfunction "1_1") (pintype "passive"))
      (node (ref "C13") (pin "2") (pinfunction "2_2") (pintype "passive"))
      (node (ref "C18") (pin "1") (pinfunction "1_1") (pintype "passive"))
      (node (ref "C19") (pin "2") (pinfunction "2_2") (pintype "passive"))
      (node (ref "C20") (pin "2") (pinfunction "2_2") (pintype "passive"))
      (node (ref "C21") (pin "2") (pinfunction "2_2") (pintype "passive"))
      (node (ref "D1") (pin "1") (pinfunction "ANODE_1") (pintype "passive"))
      (node (ref "M66") (pin "42") (pinfunction "VBAT_42") (pintype "power_in"))
      (node (ref "M66") (pin "43") (pinfunction "VBAT_43") (pintype "power_in"))
      (node (ref "MIC29302") (pin "4") (pinfunction "OUT_4") (pintype "power_in"))
      (node (ref "R13") (pin "3") (pinfunction "TAP_3") (pintype "passive"))
      (node (ref "R14") (pin "2") (pinfunction "2_2") (pintype "passive"))
      (node (ref "R2") (pin "2") (pinfunction "2_2") (pintype "passive"))
      (node (ref "SW1") (pin "1") (pinfunction "1_1") (pintype "passive"))
      (node (ref "Z1") (pin "2") (pinfunction "2_2") (pintype "passive"))
    )
    (net (code "41") (name "VCC") (class "Default")
      (node (ref "7805") (pin "1") (pinfunction "VIN_1") (pintype "passive"))
      (node (ref "C10") (pin "1") (pinfunction "1_1") (pintype "passive"))
      (node (ref "C11") (pin "2") (pinfunction "2_2") (pintype "passive"))
      (node (ref "C14") (pin "1") (pinfunction "1_1") (pintype "passive"))
      (node (ref "C23") (pin "1") (pinfunction "1_1") (pintype "passive"))
      (node (ref "C24") (pin "1") (pinfunction "1_1") (pintype "passive"))
      (node (ref "LF33") (pin "1") (pinfunction "VIN_1") (pintype "passive"))
      (node (ref "MIC29302") (pin "1") (pinfunction "ENABLE_1") (pintype "input"))
      (node (ref "MIC29302") (pin "2") (pinfunction "VIN_2") (pintype "power_in"))
      (node (ref "POW") (pin "1") (pinfunction "V+_1") (pintype "power_in"))
    )
    (net (code "42") (name "unconnected-(FT232BM-CTS-Pad22)") (class "Default")
      (node (ref "FT232BM") (pin "22") (pinfunction "CTS_22") (pintype "input"))
    )
    (net (code "43") (name "unconnected-(FT232BM-DCD-Pad19)") (class "Default")
      (node (ref "FT232BM") (pin "19") (pinfunction "DCD_19") (pintype "input"))
    )
    (net (code "44") (name "unconnected-(FT232BM-DSR-Pad20)") (class "Default")
      (node (ref "FT232BM") (pin "20") (pinfunction "DSR_20") (pintype "input"))
    )
    (net (code "45") (name "unconnected-(FT232BM-DTR-Pad21)") (class "Default")
      (node (ref "FT232BM") (pin "21") (pinfunction "DTR_21") (pintype "output"))
    )
    (net (code "46") (name "unconnected-(FT232BM-EECS-Pad32)") (class "Default")
      (node (ref "FT232BM") (pin "32") (pinfunction "EECS_32") (pintype "bidirectional"))
    )
    (net (code "47") (name "unconnected-(FT232BM-EEDATA-Pad2)") (class "Default")
      (node (ref "FT232BM") (pin "2") (pinfunction "EEDATA_2") (pintype "bidirectional"))
    )
    (net (code "48") (name "unconnected-(FT232BM-EESK-Pad1)") (class "Default")
      (node (ref "FT232BM") (pin "1") (pinfunction "EESK_1") (pintype "output"))
    )
    (net (code "49") (name "unconnected-(FT232BM-PWRCTL-Pad14)") (class "Default")
      (node (ref "FT232BM") (pin "14") (pinfunction "PWRCTL_14") (pintype "input"))
    )
    (net (code "50") (name "unconnected-(FT232BM-PWREN-Pad15)") (class "Default")
      (node (ref "FT232BM") (pin "15") (pinfunction "PWREN_15") (pintype "output"))
    )
    (net (code "51") (name "unconnected-(FT232BM-RI-Pad18)") (class "Default")
      (node (ref "FT232BM") (pin "18") (pinfunction "RI_18") (pintype "input"))
    )
    (net (code "52") (name "unconnected-(FT232BM-RTS-Pad23)") (class "Default")
      (node (ref "FT232BM") (pin "23") (pinfunction "RTS_23") (pintype "output"))
    )
    (net (code "53") (name "unconnected-(FT232BM-SLEEP-Pad10)") (class "Default")
      (node (ref "FT232BM") (pin "10") (pinfunction "SLEEP_10") (pintype "output"))
    )
    (net (code "54") (name "unconnected-(FT232BM-TEST-Pad31)") (class "Default")
      (node (ref "FT232BM") (pin "31") (pinfunction "TEST_31") (pintype "input"))
    )
    (net (code "55") (name "unconnected-(FT232BM-TXDEN-Pad16)") (class "Default")
      (node (ref "FT232BM") (pin "16") (pinfunction "TXDEN_16") (pintype "output"))
    )
    (net (code "56") (name "unconnected-(M66-ADC0-Pad9)") (class "Default")
      (node (ref "M66") (pin "9") (pinfunction "ADC0_9") (pintype "input"))
    )
    (net (code "57") (name "unconnected-(M66-AGND-Pad1)") (class "Default")
      (node (ref "M66") (pin "1") (pinfunction "AGND_1") (pintype "power_in"))
    )
    (net (code "58") (name "unconnected-(M66-AVDD-Pad8)") (class "Default")
      (node (ref "M66") (pin "8") (pinfunction "AVDD_8") (pintype "power_in"))
    )
    (net (code "59") (name "unconnected-(M66-BT_ANT-Pad26)") (class "Default")
      (node (ref "M66") (pin "26") (pinfunction "BT_ANT_26") (pintype "bidirectional"))
    )
    (net (code "60") (name "unconnected-(M66-CTS-Pad22)") (class "Default")
      (node (ref "M66") (pin "22") (pinfunction "CTS_22") (pintype "output"))
    )
    (net (code "61") (name "unconnected-(M66-DBG_RXD-Pad38)") (class "Default")
      (node (ref "M66") (pin "38") (pinfunction "DBG_RXD_38") (pintype "input"))
    )
    (net (code "62") (name "unconnected-(M66-DBG_TXD-Pad39)") (class "Default")
      (node (ref "M66") (pin "39") (pinfunction "DBG_TXD_39") (pintype "output"))
    )
    (net (code "63") (name "unconnected-(M66-DCD-Pad21)") (class "Default")
      (node (ref "M66") (pin "21") (pinfunction "DCD_21") (pintype "output"))
    )
    (net (code "64") (name "unconnected-(M66-DTR-Pad19)") (class "Default")
      (node (ref "M66") (pin "19") (pinfunction "DTR_19") (pintype "input"))
    )
    (net (code "65") (name "unconnected-(M66-MICN-Pad4)") (class "Default")
      (node (ref "M66") (pin "4") (pinfunction "MICN_4") (pintype "input"))
    )
    (net (code "66") (name "unconnected-(M66-MICP-Pad3)") (class "Default")
      (node (ref "M66") (pin "3") (pinfunction "MICP_3") (pintype "input"))
    )
    (net (code "67") (name "unconnected-(M66-PCM_CLK-Pad30)") (class "Default")
      (node (ref "M66") (pin "30") (pinfunction "PCM_CLK_30") (pintype "output"))
    )
    (net (code "68") (name "unconnected-(M66-PCM_IN-Pad32)") (class "Default")
      (node (ref "M66") (pin "32") (pinfunction "PCM_IN_32") (pintype "input"))
    )
    (net (code "69") (name "unconnected-(M66-PCM_OUT-Pad33)") (class "Default")
      (node (ref "M66") (pin "33") (pinfunction "PCM_OUT_33") (pintype "output"))
    )
    (net (code "70") (name "unconnected-(M66-PCM_SYNC-Pad31)") (class "Default")
      (node (ref "M66") (pin "31") (pinfunction "PCM_SYNC_31") (pintype "output"))
    )
    (net (code "71") (name "unconnected-(M66-RFTXMON-Pad25)") (class "Default")
      (node (ref "M66") (pin "25") (pinfunction "RFTXMON_25") (pintype "output"))
    )
    (net (code "72") (name "unconnected-(M66-RI-Pad20)") (class "Default")
      (node (ref "M66") (pin "20") (pinfunction "RI_20") (pintype "output"))
    )
    (net (code "73") (name "unconnected-(M66-RXD_AUX-Pad28)") (class "Default")
      (node (ref "M66") (pin "28") (pinfunction "RXD_AUX_28") (pintype "input"))
    )
    (net (code "74") (name "unconnected-(M66-SPK1N-Pad6)") (class "Default")
      (node (ref "M66") (pin "6") (pinfunction "SPK1N_6") (pintype "output"))
    )
    (net (code "75") (name "unconnected-(M66-SPK1P-Pad5)") (class "Default")
      (node (ref "M66") (pin "5") (pinfunction "SPK1P_5") (pintype "output"))
    )
    (net (code "76") (name "unconnected-(M66-SPK2P-Pad2)") (class "Default")
      (node (ref "M66") (pin "2") (pinfunction "SPK2P_2") (pintype "output"))
    )
    (net (code "77") (name "unconnected-(M66-TXD_AUX-Pad29)") (class "Default")
      (node (ref "M66") (pin "29") (pinfunction "TXD_AUX_29") (pintype "output"))
    )
    (net (code "78") (name "unconnected-(M66-VDD_EXT-Pad24)") (class "Default")
      (node (ref "M66") (pin "24") (pinfunction "VDD_EXT_24") (pintype "power_in"))
    )
    (net (code "79") (name "unconnected-(M66-VRTC-Pad44)") (class "Default")
      (node (ref "M66") (pin "44") (pinfunction "VRTC_44") (pintype "power_in"))
    )
    (net (code "80") (name "unconnected-(POW-GND1-Pad3)") (class "Default")
      (node (ref "POW") (pin "3") (pinfunction "GND1_3") (pintype "power_in"))
    )
    (net (code "81") (name "unconnected-(R13-TOP-Pad1)") (class "Default")
      (node (ref "R13") (pin "1") (pinfunction "TOP_1") (pintype "passive"))
    )
    (net (code "82") (name "unconnected-(SC1-VPP-PadC6)") (class "Default")
      (node (ref "SC1") (pin "C6") (pinfunction "VPP_C6") (pintype "passive"))
    )
    (net (code "83") (name "unconnected-(SMF0FC-Pad3)") (class "Default")
      (node (ref "SMF0FC") (pin "3") (pinfunction "3_3") (pintype "passive"))
    )
    (net (code "84") (name "unconnected-(SP1-Pad0)") (class "Default")
      (node (ref "SP1") (pin "0") (pinfunction "0_0") (pintype "passive"))
    )
    (net (code "85") (name "unconnected-(SP2-Pad0)") (class "Default")
      (node (ref "SP2") (pin "0") (pinfunction "0_0") (pintype "passive"))
    )
    (net (code "86") (name "unconnected-(SP3-Pad0)") (class "Default")
      (node (ref "SP3") (pin "0") (pinfunction "0_0") (pintype "passive"))
    )
    (net (code "87") (name "unconnected-(SP4-Pad0)") (class "Default")
      (node (ref "SP4") (pin "0") (pinfunction "0_0") (pintype "passive"))
    )
    (net (code "88") (name "unconnected-(SW1-PadMH1)") (class "Default")
      (node (ref "SW1") (pin "MH1") (pinfunction "MH1_MH1") (pintype "passive"))
    )
    (net (code "89") (name "unconnected-(SW1-PadMH2)") (class "Default")
      (node (ref "SW1") (pin "MH2") (pinfunction "MH2_MH2") (pintype "passive"))
    )
    (net (code "90") (name "unconnected-(USB B-Pad5)") (class "Default")
      (node (ref "USB B") (pin "5") (pinfunction "5_5") (pintype "passive"))
    )
    (net (code "91") (name "unconnected-(USB B-Pad6)") (class "Default")
      (node (ref "USB B") (pin "6") (pinfunction "6_6") (pintype "passive"))
    )
  )
)
